# wisenode_v1_0.net
KiCad netlist of a schematic drawn in EAGLE
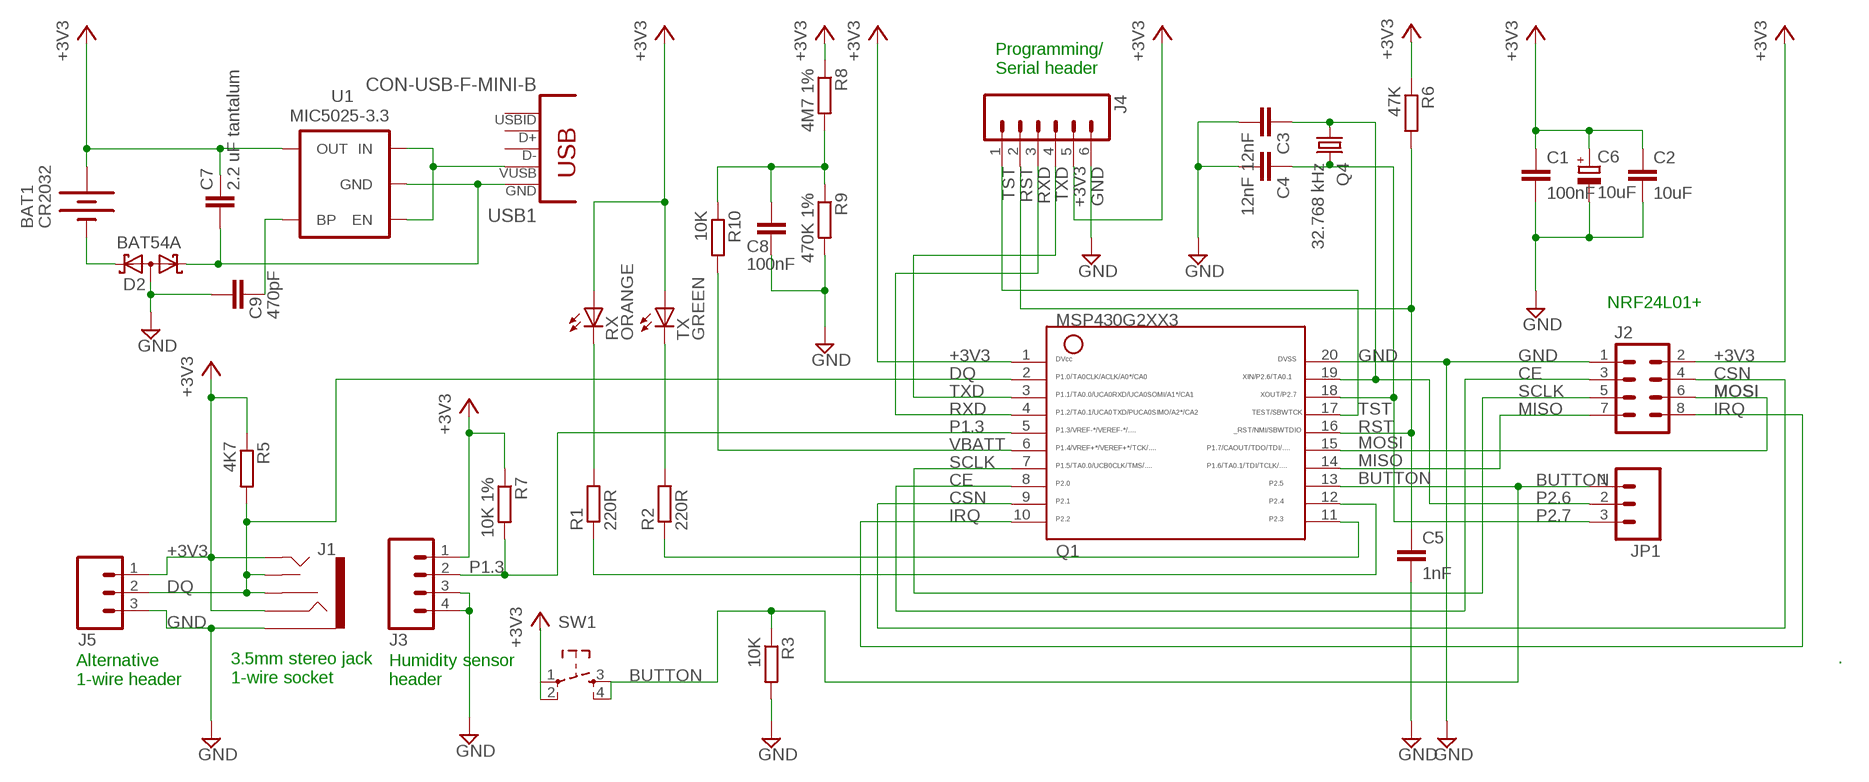
[diagram p0: schematic, sheet 1]

(export (version "E")
  (design (tool "Eeschema 10.0.6"))
  (components
    (comp (ref "BAT1")
      (value "CR2032")
      (footprint "eagle-import:BATTCOM_20MM_PTH")
      (libsource (lib "eagle-import") (part "BATTERY20PTH"))
    )
    (comp (ref "C1")
      (value "100nF")
      (footprint "eagle-import:C0805")
      (libsource (lib "eagle-import") (part "resistor_C-EUC0805"))
    )
    (comp (ref "C2")
      (value "10uF")
      (footprint "eagle-import:C1206")
      (libsource (lib "eagle-import") (part "C-EUC1206"))
    )
    (comp (ref "C3")
      (value "12nF")
      (footprint "eagle-import:C0805")
      (libsource (lib "eagle-import") (part "resistor_C-EUC0805"))
    )
    (comp (ref "C4")
      (value "12nF")
      (footprint "eagle-import:C0805")
      (libsource (lib "eagle-import") (part "resistor_C-EUC0805"))
    )
    (comp (ref "C5")
      (value "1nF")
      (footprint "eagle-import:C0805")
      (libsource (lib "eagle-import") (part "resistor_C-EUC0805"))
    )
    (comp (ref "C6")
      (value "10uF")
      (footprint "eagle-import:E2,5-7")
      (libsource (lib "eagle-import") (part "CPOL-EUE2.5-7"))
    )
    (comp (ref "C7")
      (value "2.2 uF tantalum")
      (footprint "eagle-import:C1206")
      (libsource (lib "eagle-import") (part "C-EUC1206"))
    )
    (comp (ref "C8")
      (value "100nF")
      (footprint "eagle-import:C0805")
      (libsource (lib "eagle-import") (part "resistor_C-EUC0805"))
    )
    (comp (ref "C9")
      (value "470pF")
      (footprint "eagle-import:C0805")
      (libsource (lib "eagle-import") (part "resistor_C-EUC0805"))
    )
    (comp (ref "D2")
      (value "BAT54A")
      (footprint "eagle-import:SOT23")
      (libsource (lib "eagle-import") (part "BAT54A"))
    )
    (comp (ref "J1")
      (value "AUDIO-JACK2PTH")
      (footprint "eagle-import:AUDIO-JACK")
      (libsource (lib "eagle-import") (part "AUDIO-JACK2PTH"))
    )
    (comp (ref "J2")
      (value "M04X2")
      (footprint "eagle-import:2X4")
      (libsource (lib "eagle-import") (part "M04X2"))
    )
    (comp (ref "J3")
      (value "M04PTH")
      (footprint "eagle-import:1X04")
      (libsource (lib "eagle-import") (part "M04PTH"))
    )
    (comp (ref "J4")
      (value "M06SIP")
      (footprint "eagle-import:1X06")
      (libsource (lib "eagle-import") (part "M06SIP"))
    )
    (comp (ref "J5")
      (value "M03PTH")
      (footprint "eagle-import:1X03")
      (libsource (lib "eagle-import") (part "M03PTH"))
    )
    (comp (ref "JP1")
      (value "M03PTH")
      (footprint "eagle-import:1X03")
      (libsource (lib "eagle-import") (part "M03PTH"))
    )
    (comp (ref "Q1")
      (value "G2XX3---PW20")
      (footprint "eagle-import:PW20")
      (libsource (lib "eagle-import") (part "G2XX3---PW20"))
    )
    (comp (ref "Q4")
      (value "32.768 kHz")
      (footprint "eagle-import:TC38H")
      (libsource (lib "eagle-import") (part "CRYSTALTC38H"))
    )
    (comp (ref "R1")
      (value "220R")
      (footprint "eagle-import:M0805")
      (fields (field (name "RESISTANCE") "4K7"))
      (libsource (lib "eagle-import") (part "R-EU_M0805"))
    )
    (comp (ref "R2")
      (value "220R")
      (footprint "eagle-import:M0805")
      (fields (field (name "RESISTANCE") "4K7"))
      (libsource (lib "eagle-import") (part "R-EU_M0805"))
    )
    (comp (ref "R3")
      (value "10K")
      (footprint "eagle-import:M0805")
      (fields (field (name "RESISTANCE") "4K7"))
      (libsource (lib "eagle-import") (part "R-EU_M0805"))
    )
    (comp (ref "R5")
      (value "4K7")
      (footprint "eagle-import:M0805")
      (fields (field (name "RESISTANCE") "4K7"))
      (libsource (lib "eagle-import") (part "R-EU_M0805"))
    )
    (comp (ref "R6")
      (value "47K")
      (footprint "eagle-import:M0805")
      (fields (field (name "RESISTANCE") "4K7"))
      (libsource (lib "eagle-import") (part "R-EU_M0805"))
    )
    (comp (ref "R7")
      (value "10K 1%")
      (footprint "eagle-import:M0805")
      (fields (field (name "RESISTANCE") "4K7"))
      (libsource (lib "eagle-import") (part "R-EU_M0805"))
    )
    (comp (ref "R8")
      (value "4M7 1%")
      (footprint "eagle-import:M0805")
      (fields (field (name "RESISTANCE") "4K7"))
      (libsource (lib "eagle-import") (part "R-EU_M0805"))
    )
    (comp (ref "R9")
      (value "470K 1%")
      (footprint "eagle-import:M0805")
      (fields (field (name "RESISTANCE") "4K7"))
      (libsource (lib "eagle-import") (part "R-EU_M0805"))
    )
    (comp (ref "R10")
      (value "10K")
      (footprint "eagle-import:M0805")
      (fields (field (name "RESISTANCE") "4K7"))
      (libsource (lib "eagle-import") (part "R-EU_M0805"))
    )
    (comp (ref "RX")
      (value "ORANGE")
      (footprint "eagle-import:CHIPLED_0805")
      (libsource (lib "eagle-import") (part "LEDCHIPLED_0805"))
    )
    (comp (ref "SW1")
      (value "SW_TACT_4P")
      (footprint "eagle-import:SW_TACT_SMALL")
      (libsource (lib "eagle-import") (part "SW_TACT_4P"))
    )
    (comp (ref "TX")
      (value "GREEN")
      (footprint "eagle-import:CHIPLED_0805")
      (libsource (lib "eagle-import") (part "LEDCHIPLED_0805"))
    )
    (comp (ref "U1")
      (value "MIC5025-3.3")
      (footprint "eagle-import:SOT23-5")
      (libsource (lib "eagle-import") (part "V_REG_LDOSMD"))
    )
    (comp (ref "USB1")
      (value "CON-USB-F-MINI-B")
      (footprint "eagle-import:CONN_USB_MINI-B")
      (libsource (lib "eagle-import") (part "CON-USB-F-MINI-B"))
    )
  )
  (nets
    (net (code "1") (name "+3V3") (class "Default")
      (node (ref "BAT1") (pin "1") (pinfunction "+_1") (pintype "power_in"))
      (node (ref "C1") (pin "1") (pinfunction "1_1") (pintype "passive"))
      (node (ref "C2") (pin "1") (pinfunction "1_1") (pintype "passive"))
      (node (ref "C6") (pin "+") (pinfunction "+_+") (pintype "passive"))
      (node (ref "C7") (pin "1") (pinfunction "1_1") (pintype "passive"))
      (node (ref "J1") (pin "RING") (pinfunction "RING_RING") (pintype "bidirectional"))
      (node (ref "J1") (pin "TIP") (pinfunction "TIP_TIP") (pintype "bidirectional"))
      (node (ref "J2") (pin "2") (pinfunction "2_2") (pintype "passive"))
      (node (ref "J3") (pin "1") (pinfunction "1_1") (pintype "passive"))
      (node (ref "J4") (pin "5") (pinfunction "5_5") (pintype "passive"))
      (node (ref "J5") (pin "1") (pinfunction "1_1") (pintype "passive"))
      (node (ref "Q1") (pin "1") (pinfunction "1_1") (pintype "bidirectional"))
      (node (ref "R5") (pin "1") (pinfunction "1_1") (pintype "passive"))
      (node (ref "R6") (pin "1") (pinfunction "1_1") (pintype "passive"))
      (node (ref "R7") (pin "1") (pinfunction "1_1") (pintype "passive"))
      (node (ref "R8") (pin "1") (pinfunction "1_1") (pintype "passive"))
      (node (ref "RX") (pin "A") (pinfunction "A_A") (pintype "passive"))
      (node (ref "SW1") (pin "1") (pinfunction "1_1") (pintype "passive"))
      (node (ref "SW1") (pin "2") (pinfunction "2_2") (pintype "passive"))
      (node (ref "TX") (pin "A") (pinfunction "A_A") (pintype "passive"))
      (node (ref "U1") (pin "5") (pinfunction "OUT_5") (pintype "passive"))
    )
    (net (code "2") (name "/BUTTON") (class "Default")
      (node (ref "JP1") (pin "1") (pinfunction "1_1") (pintype "passive"))
      (node (ref "Q1") (pin "13") (pinfunction "13_13") (pintype "bidirectional"))
      (node (ref "R3") (pin "1") (pinfunction "1_1") (pintype "passive"))
      (node (ref "SW1") (pin "3") (pinfunction "3_3") (pintype "passive"))
      (node (ref "SW1") (pin "4") (pinfunction "4_4") (pintype "passive"))
    )
    (net (code "3") (name "/CE") (class "Default")
      (node (ref "J2") (pin "3") (pinfunction "3_3") (pintype "passive"))
      (node (ref "Q1") (pin "8") (pinfunction "8_8") (pintype "bidirectional"))
    )
    (net (code "4") (name "/CSN") (class "Default")
      (node (ref "J2") (pin "4") (pinfunction "4_4") (pintype "passive"))
      (node (ref "Q1") (pin "9") (pinfunction "9_9") (pintype "bidirectional"))
    )
    (net (code "5") (name "/DQ") (class "Default")
      (node (ref "J1") (pin "RSH") (pinfunction "RSH_RSH") (pintype "bidirectional"))
      (node (ref "J1") (pin "TSH") (pinfunction "TSH_TSH") (pintype "bidirectional"))
      (node (ref "J5") (pin "2") (pinfunction "2_2") (pintype "passive"))
      (node (ref "Q1") (pin "2") (pinfunction "2_2") (pintype "bidirectional"))
      (node (ref "R5") (pin "2") (pinfunction "2_2") (pintype "passive"))
    )
    (net (code "6") (name "/IRQ") (class "Default")
      (node (ref "J2") (pin "8") (pinfunction "8_8") (pintype "passive"))
      (node (ref "Q1") (pin "10") (pinfunction "10_10") (pintype "bidirectional"))
    )
    (net (code "7") (name "/MISO") (class "Default")
      (node (ref "J2") (pin "7") (pinfunction "7_7") (pintype "passive"))
      (node (ref "Q1") (pin "14") (pinfunction "14_14") (pintype "bidirectional"))
    )
    (net (code "8") (name "/MOSI") (class "Default")
      (node (ref "J2") (pin "6") (pinfunction "6_6") (pintype "passive"))
      (node (ref "Q1") (pin "15") (pinfunction "15_15") (pintype "bidirectional"))
    )
    (net (code "9") (name "/P1.3") (class "Default")
      (node (ref "J3") (pin "2") (pinfunction "2_2") (pintype "passive"))
      (node (ref "Q1") (pin "5") (pinfunction "5_5") (pintype "bidirectional"))
      (node (ref "R7") (pin "2") (pinfunction "2_2") (pintype "passive"))
    )
    (net (code "10") (name "/P2.6") (class "Default")
      (node (ref "C3") (pin "1") (pinfunction "1_1") (pintype "passive"))
      (node (ref "JP1") (pin "2") (pinfunction "2_2") (pintype "passive"))
      (node (ref "Q1") (pin "19") (pinfunction "19_19") (pintype "bidirectional"))
      (node (ref "Q4") (pin "1") (pinfunction "1_1") (pintype "passive"))
    )
    (net (code "11") (name "/P2.7") (class "Default")
      (node (ref "C4") (pin "1") (pinfunction "1_1") (pintype "passive"))
      (node (ref "JP1") (pin "3") (pinfunction "3_3") (pintype "passive"))
      (node (ref "Q1") (pin "18") (pinfunction "18_18") (pintype "bidirectional"))
      (node (ref "Q4") (pin "2") (pinfunction "2_2") (pintype "passive"))
    )
    (net (code "12") (name "/RST") (class "Default")
      (node (ref "C5") (pin "1") (pinfunction "1_1") (pintype "passive"))
      (node (ref "J4") (pin "2") (pinfunction "2_2") (pintype "passive"))
      (node (ref "Q1") (pin "16") (pinfunction "16_16") (pintype "bidirectional"))
      (node (ref "R6") (pin "2") (pinfunction "2_2") (pintype "passive"))
    )
    (net (code "13") (name "/RXD") (class "Default")
      (node (ref "J4") (pin "3") (pinfunction "3_3") (pintype "passive"))
      (node (ref "Q1") (pin "4") (pinfunction "4_4") (pintype "bidirectional"))
    )
    (net (code "14") (name "/SCLK") (class "Default")
      (node (ref "J2") (pin "5") (pinfunction "5_5") (pintype "passive"))
      (node (ref "Q1") (pin "7") (pinfunction "7_7") (pintype "bidirectional"))
    )
    (net (code "15") (name "/TST") (class "Default")
      (node (ref "J4") (pin "1") (pinfunction "1_1") (pintype "passive"))
      (node (ref "Q1") (pin "17") (pinfunction "17_17") (pintype "bidirectional"))
    )
    (net (code "16") (name "/TXD") (class "Default")
      (node (ref "J4") (pin "4") (pinfunction "4_4") (pintype "passive"))
      (node (ref "Q1") (pin "3") (pinfunction "3_3") (pintype "bidirectional"))
    )
    (net (code "17") (name "/VBATT") (class "Default")
      (node (ref "Q1") (pin "6") (pinfunction "6_6") (pintype "bidirectional"))
      (node (ref "R10") (pin "2") (pinfunction "2_2") (pintype "passive"))
    )
    (net (code "18") (name "GND") (class "Default")
      (node (ref "C1") (pin "2") (pinfunction "2_2") (pintype "passive"))
      (node (ref "C2") (pin "2") (pinfunction "2_2") (pintype "passive"))
      (node (ref "C3") (pin "2") (pinfunction "2_2") (pintype "passive"))
      (node (ref "C4") (pin "2") (pinfunction "2_2") (pintype "passive"))
      (node (ref "C5") (pin "2") (pinfunction "2_2") (pintype "passive"))
      (node (ref "C6") (pin "-") (pinfunction "-_-") (pintype "passive"))
      (node (ref "C8") (pin "2") (pinfunction "2_2") (pintype "passive"))
      (node (ref "C9") (pin "1") (pinfunction "1_1") (pintype "passive"))
      (node (ref "D2") (pin "3") (pinfunction "AA_3") (pintype "passive"))
      (node (ref "J1") (pin "SLEEVE") (pinfunction "SLEEVE_SLEEVE") (pintype "bidirectional"))
      (node (ref "J2") (pin "1") (pinfunction "1_1") (pintype "passive"))
      (node (ref "J3") (pin "3") (pinfunction "3_3") (pintype "passive"))
      (node (ref "J3") (pin "4") (pinfunction "4_4") (pintype "passive"))
      (node (ref "J4") (pin "6") (pinfunction "6_6") (pintype "passive"))
      (node (ref "J5") (pin "3") (pinfunction "3_3") (pintype "passive"))
      (node (ref "Q1") (pin "20") (pinfunction "20_20") (pintype "bidirectional"))
      (node (ref "R3") (pin "2") (pinfunction "2_2") (pintype "passive"))
      (node (ref "R9") (pin "2") (pinfunction "2_2") (pintype "passive"))
    )
    (net (code "19") (name "Net-(BAT1--)") (class "Default")
      (node (ref "BAT1") (pin "2") (pinfunction "-_2") (pintype "power_in"))
      (node (ref "D2") (pin "2") (pinfunction "K2_2") (pintype "passive"))
    )
    (net (code "20") (name "Net-(C8-Pad1)") (class "Default")
      (node (ref "C8") (pin "1") (pinfunction "1_1") (pintype "passive"))
      (node (ref "R10") (pin "1") (pinfunction "1_1") (pintype "passive"))
      (node (ref "R8") (pin "2") (pinfunction "2_2") (pintype "passive"))
      (node (ref "R9") (pin "1") (pinfunction "1_1") (pintype "passive"))
    )
    (net (code "21") (name "Net-(D2-K1)") (class "Default")
      (node (ref "C7") (pin "2") (pinfunction "2_2") (pintype "passive"))
      (node (ref "D2") (pin "1") (pinfunction "K1_1") (pintype "passive"))
      (node (ref "U1") (pin "2") (pinfunction "GND_2") (pintype "input"))
      (node (ref "USB1") (pin "GND") (pinfunction "GND_GND") (pintype "bidirectional"))
    )
    (net (code "22") (name "Net-(Q1-Pad11)") (class "Default")
      (node (ref "Q1") (pin "11") (pinfunction "11_11") (pintype "bidirectional"))
      (node (ref "R2") (pin "1") (pinfunction "1_1") (pintype "passive"))
    )
    (net (code "23") (name "Net-(Q1-Pad12)") (class "Default")
      (node (ref "Q1") (pin "12") (pinfunction "12_12") (pintype "bidirectional"))
      (node (ref "R1") (pin "1") (pinfunction "1_1") (pintype "passive"))
    )
    (net (code "24") (name "Net-(R1-Pad2)") (class "Default")
      (node (ref "R1") (pin "2") (pinfunction "2_2") (pintype "passive"))
      (node (ref "RX") (pin "C") (pinfunction "C_C") (pintype "passive"))
    )
    (net (code "25") (name "Net-(R2-Pad2)") (class "Default")
      (node (ref "R2") (pin "2") (pinfunction "2_2") (pintype "passive"))
      (node (ref "TX") (pin "C") (pinfunction "C_C") (pintype "passive"))
    )
    (net (code "26") (name "Net-(U1-BP)") (class "Default")
      (node (ref "C9") (pin "2") (pinfunction "2_2") (pintype "passive"))
      (node (ref "U1") (pin "4") (pinfunction "BP_4") (pintype "input"))
    )
    (net (code "27") (name "Net-(U1-EN)") (class "Default")
      (node (ref "U1") (pin "1") (pinfunction "IN_1") (pintype "input"))
      (node (ref "U1") (pin "3") (pinfunction "EN_3") (pintype "input"))
      (node (ref "USB1") (pin "VUSB") (pinfunction "VUSB_VUSB") (pintype "bidirectional"))
    )
    (net (code "28") (name "unconnected-(USB1-PadD+)") (class "Default")
      (node (ref "USB1") (pin "D+") (pinfunction "D+_D+") (pintype "bidirectional"))
    )
    (net (code "29") (name "unconnected-(USB1-PadD-)") (class "Default")
      (node (ref "USB1") (pin "D-") (pinfunction "D-_D-") (pintype "bidirectional"))
    )
    (net (code "30") (name "unconnected-(USB1B-USBID-PadID)") (class "Default")
      (node (ref "USB1") (pin "ID") (pinfunction "USBID_ID") (pintype "bidirectional"))
    )
  )
)
